# OLED.net
KiCad netlist of a schematic drawn in Altium Designer
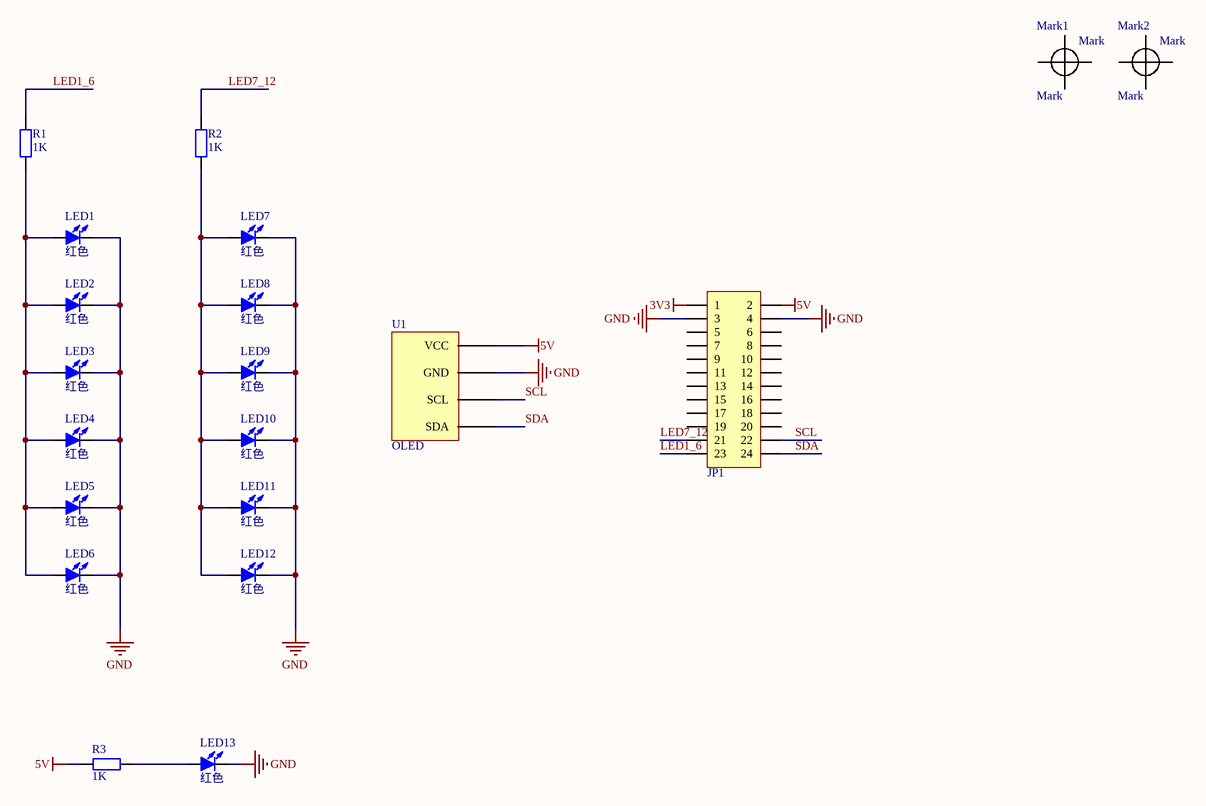
[diagram p0: OLED.SchDoc]

(export (version "E")
  (design (tool "Eeschema 10.0.6"))
  (components
    (comp (ref "JP1")
      (value "Header 2X11")
      (footprint "HDR2.54-WI-2x12P")
      (description "12*2P接插件")
      (fields (field (name "版权归属") "封装库来自淘宝卖家 ID：黄晶宝石"))
      (libsource (lib "5.4 - 接插件-脚距2.54 (100mil) ") (part "Header 12X2"))
    )
    (comp (ref "LED1")
      (value "红色")
      (footprint "LED 0603R")
      (description "贴片LED")
      (fields (field (name "版权归属") "封装库来自淘宝 ID：黄晶宝石"))
      (libsource (lib "0.3 - LED发光二极管") (part "LED-SMD"))
    )
    (comp (ref "LED2")
      (value "红色")
      (footprint "LED 0603R")
      (description "贴片LED")
      (fields (field (name "版权归属") "封装库来自淘宝 ID：黄晶宝石"))
      (libsource (lib "0.3 - LED发光二极管") (part "LED-SMD"))
    )
    (comp (ref "LED3")
      (value "红色")
      (footprint "LED 0603R")
      (description "贴片LED")
      (fields (field (name "版权归属") "封装库来自淘宝 ID：黄晶宝石"))
      (libsource (lib "0.3 - LED发光二极管") (part "LED-SMD"))
    )
    (comp (ref "LED4")
      (value "红色")
      (footprint "LED 0603R")
      (description "贴片LED")
      (fields (field (name "版权归属") "封装库来自淘宝 ID：黄晶宝石"))
      (libsource (lib "0.3 - LED发光二极管") (part "LED-SMD"))
    )
    (comp (ref "LED5")
      (value "红色")
      (footprint "LED 0603R")
      (description "贴片LED")
      (fields (field (name "版权归属") "封装库来自淘宝 ID：黄晶宝石"))
      (libsource (lib "0.3 - LED发光二极管") (part "LED-SMD"))
    )
    (comp (ref "LED6")
      (value "红色")
      (footprint "LED 0603R")
      (description "贴片LED")
      (fields (field (name "版权归属") "封装库来自淘宝 ID：黄晶宝石"))
      (libsource (lib "0.3 - LED发光二极管") (part "LED-SMD"))
    )
    (comp (ref "LED7")
      (value "红色")
      (footprint "LED 0603R")
      (description "贴片LED")
      (fields (field (name "版权归属") "封装库来自淘宝 ID：黄晶宝石"))
      (libsource (lib "0.3 - LED发光二极管") (part "LED-SMD"))
    )
    (comp (ref "LED8")
      (value "红色")
      (footprint "LED 0603R")
      (description "贴片LED")
      (fields (field (name "版权归属") "封装库来自淘宝 ID：黄晶宝石"))
      (libsource (lib "0.3 - LED发光二极管") (part "LED-SMD"))
    )
    (comp (ref "LED9")
      (value "红色")
      (footprint "LED 0603R")
      (description "贴片LED")
      (fields (field (name "版权归属") "封装库来自淘宝 ID：黄晶宝石"))
      (libsource (lib "0.3 - LED发光二极管") (part "LED-SMD"))
    )
    (comp (ref "LED10")
      (value "红色")
      (footprint "LED 0603R")
      (description "贴片LED")
      (fields (field (name "版权归属") "封装库来自淘宝 ID：黄晶宝石"))
      (libsource (lib "0.3 - LED发光二极管") (part "LED-SMD"))
    )
    (comp (ref "LED11")
      (value "红色")
      (footprint "LED 0603R")
      (description "贴片LED")
      (fields (field (name "版权归属") "封装库来自淘宝 ID：黄晶宝石"))
      (libsource (lib "0.3 - LED发光二极管") (part "LED-SMD"))
    )
    (comp (ref "LED12")
      (value "红色")
      (footprint "LED 0603R")
      (description "贴片LED")
      (fields (field (name "版权归属") "封装库来自淘宝 ID：黄晶宝石"))
      (libsource (lib "0.3 - LED发光二极管") (part "LED-SMD"))
    )
    (comp (ref "LED13")
      (value "红色")
      (footprint "LED 0603R")
      (description "贴片LED")
      (fields (field (name "版权归属") "封装库来自淘宝 ID：黄晶宝石"))
      (libsource (lib "0.3 - LED发光二极管") (part "LED-SMD"))
    )
    (comp (ref "Mark1") (value "Mark") (footprint "Mark:Mark") (libsource (lib "Mark") (part "Mark")))
    (comp (ref "Mark2") (value "Mark") (footprint "Mark:Mark") (libsource (lib "Mark") (part "Mark")))
    (comp (ref "R1")
      (value "1K")
      (footprint "R 0603_L")
      (description "贴片电阻")
      (fields (field (name "版权归属") "来自淘宝 ID：黄晶宝石"))
      (libsource (lib "0.1 - 电阻-电容-电感") (part "R"))
    )
    (comp (ref "R2")
      (value "1K")
      (footprint "R 0603_L")
      (description "贴片电阻")
      (fields (field (name "版权归属") "来自淘宝 ID：黄晶宝石"))
      (libsource (lib "0.1 - 电阻-电容-电感") (part "R"))
    )
    (comp (ref "R3")
      (value "1K")
      (footprint "R 0603_L")
      (description "贴片电阻")
      (fields (field (name "版权归属") "来自淘宝 ID：黄晶宝石"))
      (libsource (lib "0.1 - 电阻-电容-电感") (part "R"))
    )
    (comp (ref "U1") (value "OLED") (footprint "4pinOLED") (libsource (lib "Schlib1") (part "OLED")))
  )
  (nets
    (net (code "1") (name "/LED1_6") (class "Default")
      (node (ref "JP1") (pin "23") (pinfunction "23_23") (pintype "passive"))
      (node (ref "R1") (pin "2") (pinfunction "2_2") (pintype "passive"))
    )
    (net (code "2") (name "/LED7_12") (class "Default")
      (node (ref "JP1") (pin "21") (pinfunction "21_21") (pintype "passive"))
      (node (ref "R2") (pin "2") (pinfunction "2_2") (pintype "passive"))
    )
    (net (code "3") (name "/SCL") (class "Default")
      (node (ref "JP1") (pin "22") (pinfunction "22_22") (pintype "passive"))
      (node (ref "U1") (pin "3") (pinfunction "SCL_3") (pintype "passive"))
    )
    (net (code "4") (name "/SDA") (class "Default")
      (node (ref "JP1") (pin "24") (pinfunction "24_24") (pintype "passive"))
      (node (ref "U1") (pin "4") (pinfunction "SDA_4") (pintype "passive"))
    )
    (net (code "5") (name "3V3") (class "Default")
      (node (ref "JP1") (pin "1") (pinfunction "1_1") (pintype "passive"))
    )
    (net (code "6") (name "5V") (class "Default")
      (node (ref "JP1") (pin "2") (pinfunction "2_2") (pintype "passive"))
      (node (ref "R3") (pin "2") (pinfunction "2_2") (pintype "passive"))
      (node (ref "U1") (pin "1") (pinfunction "VCC_1") (pintype "passive"))
    )
    (net (code "7") (name "GND") (class "Default")
      (node (ref "JP1") (pin "3") (pinfunction "3_3") (pintype "passive"))
      (node (ref "JP1") (pin "4") (pinfunction "4_4") (pintype "passive"))
      (node (ref "LED1") (pin "2") (pinfunction "K_2") (pintype "passive"))
      (node (ref "LED10") (pin "2") (pinfunction "K_2") (pintype "passive"))
      (node (ref "LED11") (pin "2") (pinfunction "K_2") (pintype "passive"))
      (node (ref "LED12") (pin "2") (pinfunction "K_2") (pintype "passive"))
      (node (ref "LED13") (pin "2") (pinfunction "K_2") (pintype "passive"))
      (node (ref "LED2") (pin "2") (pinfunction "K_2") (pintype "passive"))
      (node (ref "LED3") (pin "2") (pinfunction "K_2") (pintype "passive"))
      (node (ref "LED4") (pin "2") (pinfunction "K_2") (pintype "passive"))
      (node (ref "LED5") (pin "2") (pinfunction "K_2") (pintype "passive"))
      (node (ref "LED6") (pin "2") (pinfunction "K_2") (pintype "passive"))
      (node (ref "LED7") (pin "2") (pinfunction "K_2") (pintype "passive"))
      (node (ref "LED8") (pin "2") (pinfunction "K_2") (pintype "passive"))
      (node (ref "LED9") (pin "2") (pinfunction "K_2") (pintype "passive"))
      (node (ref "U1") (pin "2") (pinfunction "GND_2") (pintype "passive"))
    )
    (net (code "8") (name "Net-(LED1-A)") (class "Default")
      (node (ref "LED1") (pin "1") (pinfunction "A_1") (pintype "passive"))
      (node (ref "LED2") (pin "1") (pinfunction "A_1") (pintype "passive"))
      (node (ref "LED3") (pin "1") (pinfunction "A_1") (pintype "passive"))
      (node (ref "LED4") (pin "1") (pinfunction "A_1") (pintype "passive"))
      (node (ref "LED5") (pin "1") (pinfunction "A_1") (pintype "passive"))
      (node (ref "LED6") (pin "1") (pinfunction "A_1") (pintype "passive"))
      (node (ref "R1") (pin "1") (pinfunction "1_1") (pintype "passive"))
    )
    (net (code "9") (name "Net-(LED10-A)") (class "Default")
      (node (ref "LED10") (pin "1") (pinfunction "A_1") (pintype "passive"))
      (node (ref "LED11") (pin "1") (pinfunction "A_1") (pintype "passive"))
      (node (ref "LED12") (pin "1") (pinfunction "A_1") (pintype "passive"))
      (node (ref "LED7") (pin "1") (pinfunction "A_1") (pintype "passive"))
      (node (ref "LED8") (pin "1") (pinfunction "A_1") (pintype "passive"))
      (node (ref "LED9") (pin "1") (pinfunction "A_1") (pintype "passive"))
      (node (ref "R2") (pin "1") (pinfunction "1_1") (pintype "passive"))
    )
    (net (code "10") (name "Net-(LED13-A)") (class "Default")
      (node (ref "LED13") (pin "1") (pinfunction "A_1") (pintype "passive"))
      (node (ref "R3") (pin "1") (pinfunction "1_1") (pintype "passive"))
    )
    (net (code "11") (name "unconnected-(JP1-Pad5)") (class "Default")
      (node (ref "JP1") (pin "5") (pinfunction "5_5") (pintype "passive"))
    )
    (net (code "12") (name "unconnected-(JP1-Pad6)") (class "Default")
      (node (ref "JP1") (pin "6") (pinfunction "6_6") (pintype "passive"))
    )
    (net (code "13") (name "unconnected-(JP1-Pad7)") (class "Default")
      (node (ref "JP1") (pin "7") (pinfunction "7_7") (pintype "passive"))
    )
    (net (code "14") (name "unconnected-(JP1-Pad8)") (class "Default")
      (node (ref "JP1") (pin "8") (pinfunction "8_8") (pintype "passive"))
    )
    (net (code "15") (name "unconnected-(JP1-Pad9)") (class "Default")
      (node (ref "JP1") (pin "9") (pinfunction "9_9") (pintype "passive"))
    )
    (net (code "16") (name "unconnected-(JP1-Pad10)") (class "Default")
      (node (ref "JP1") (pin "10") (pinfunction "10_10") (pintype "passive"))
    )
    (net (code "17") (name "unconnected-(JP1-Pad11)") (class "Default")
      (node (ref "JP1") (pin "11") (pinfunction "11_11") (pintype "passive"))
    )
    (net (code "18") (name "unconnected-(JP1-Pad12)") (class "Default")
      (node (ref "JP1") (pin "12") (pinfunction "12_12") (pintype "passive"))
    )
    (net (code "19") (name "unconnected-(JP1-Pad13)") (class "Default")
      (node (ref "JP1") (pin "13") (pinfunction "13_13") (pintype "passive"))
    )
    (net (code "20") (name "unconnected-(JP1-Pad14)") (class "Default")
      (node (ref "JP1") (pin "14") (pinfunction "14_14") (pintype "passive"))
    )
    (net (code "21") (name "unconnected-(JP1-Pad15)") (class "Default")
      (node (ref "JP1") (pin "15") (pinfunction "15_15") (pintype "passive"))
    )
    (net (code "22") (name "unconnected-(JP1-Pad16)") (class "Default")
      (node (ref "JP1") (pin "16") (pinfunction "16_16") (pintype "passive"))
    )
    (net (code "23") (name "unconnected-(JP1-Pad17)") (class "Default")
      (node (ref "JP1") (pin "17") (pinfunction "17_17") (pintype "passive"))
    )
    (net (code "24") (name "unconnected-(JP1-Pad18)") (class "Default")
      (node (ref "JP1") (pin "18") (pinfunction "18_18") (pintype "passive"))
    )
    (net (code "25") (name "unconnected-(JP1-Pad19)") (class "Default")
      (node (ref "JP1") (pin "19") (pinfunction "19_19") (pintype "passive"))
    )
    (net (code "26") (name "unconnected-(JP1-Pad20)") (class "Default")
      (node (ref "JP1") (pin "20") (pinfunction "20_20") (pintype "passive"))
    )
  )
)
